# node-circuits.net
KiCad netlist of a schematic drawn in Altium Designer
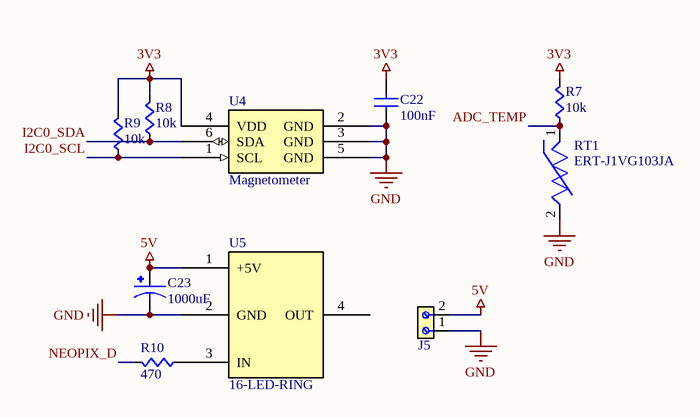
[diagram p0: node-circuits.SchDoc]

(export (version "E")
  (design (tool "Eeschema 10.0.6"))
  (components
    (comp (ref "C22")
      (value "100nF")
      (footprint "CAPC0603")
      (fields (field (name "Comment") "Cap"))
      (libsource (lib "Passives") (part "Cap"))
    )
    (comp (ref "C23")
      (value "1000uF")
      (footprint "CAPPRD350W60D800H1150")
      (description "EEUFM1H101. Cap Aluminum Lytic 100uF 50V 20% (8 X 11.5mm) Radial 3.5mm 870mA 3000h 105?ÂÂŽ Bulk")
      (fields (field (name "MP") "EEUFM1H101") (field (name "MF") "Panasonic"))
      (libsource (lib "Alexandria") (part "EEUFM1H101"))
    )
    (comp (ref "J5")
      (value "[Connector] 691213510002")
      (footprint "[CONNECTOR] 5MM_2PORT_SCREW")
      (description "2 Position Wire to Board Terminal Block Horizontal with Board 0.200 (5.08mm) Through Hole")
      (fields (field (name "MF") "WÃ¼rth Elektronik") (field (name "MP") "691213510002"))
      (libsource (lib "Alexandria") (part "[Connector] 691213510002"))
    )
    (comp (ref "R7")
      (value "10k")
      (footprint "RES0603")
      (description "SMD, RES0603")
      (fields (field (name "Comment") "Res"))
      (libsource (lib "Passives") (part "Res"))
    )
    (comp (ref "R8")
      (value "10k")
      (footprint "RES0603")
      (description "SMD, RES0603")
      (fields (field (name "Comment") "Res"))
      (libsource (lib "Passives") (part "Res"))
    )
    (comp (ref "R9")
      (value "10k")
      (footprint "RES0603")
      (description "SMD, RES0603")
      (fields (field (name "Comment") "Res"))
      (libsource (lib "Passives") (part "Res"))
    )
    (comp (ref "R10")
      (value "470")
      (footprint "RES0603")
      (description "SMD, RES0603")
      (fields (field (name "Comment") "Res"))
      (libsource (lib "Passives") (part "Res"))
    )
    (comp (ref "RT1")
      (value "ERT-J1VG103JA")
      (footprint "THERM_ERT-J1VG103JA")
      (fields (field (name "MF") "Panasonic Electronic"))
      (libsource (lib "Alexandria") (part "ERT-J1VG103JA"))
    )
    (comp (ref "U4")
      (value "Magnetometer")
      (footprint "PG-TSOP6-6-5_INF")
      (fields
        (field (name "MANUFACTURER_PART_NUMBER") "TLV493DA1B6HTSA2")
        (field (name "COPYRIGHT") "Copyright (C) 2025 Ultra Librarian. All rights reserved.")
      )
      (libsource (lib "Alexandria") (part "TLV493DA1B6HTSA2"))
    )
    (comp (ref "U5")
      (value "16-LED-RING")
      (footprint "WS2812-16-RING")
      (description "16-LED Ring, RGB WS2812 neopixels")
      (libsource (lib "Alexandria") (part "WS2812B-16-LED-RING"))
    )
  )
  (nets
    (net (code "1") (name "/ADC_TEMP") (class "Default")
      (node (ref "R7") (pin "2") (pinfunction "B_2") (pintype "passive"))
      (node (ref "RT1") (pin "1") (pinfunction "1_1") (pintype "passive"))
    )
    (net (code "2") (name "/I2C0_SCL") (class "Default")
      (node (ref "R9") (pin "2") (pinfunction "B_2") (pintype "passive"))
      (node (ref "U4") (pin "1") (pinfunction "SCL_1") (pintype "input"))
    )
    (net (code "3") (name "/I2C0_SDA") (class "Default")
      (node (ref "R8") (pin "2") (pinfunction "B_2") (pintype "passive"))
      (node (ref "U4") (pin "6") (pinfunction "SDA_6") (pintype "bidirectional"))
    )
    (net (code "4") (name "/NEOPIX_D") (class "Default")
      (node (ref "R10") (pin "1") (pinfunction "A_1") (pintype "passive"))
    )
    (net (code "5") (name "3V3") (class "Default")
      (node (ref "C22") (pin "1") (pinfunction "A_1") (pintype "passive"))
      (node (ref "R7") (pin "1") (pinfunction "A_1") (pintype "passive"))
      (node (ref "R8") (pin "1") (pinfunction "A_1") (pintype "passive"))
      (node (ref "R9") (pin "1") (pinfunction "A_1") (pintype "passive"))
      (node (ref "U4") (pin "4") (pinfunction "VDD_4") (pintype "power_in"))
    )
    (net (code "6") (name "5V") (class "Default")
      (node (ref "C23") (pin "P") (pinfunction "P_P") (pintype "passive"))
      (node (ref "J5") (pin "2") (pinfunction "2_2") (pintype "passive"))
      (node (ref "U5") (pin "1") (pinfunction "+5V_1") (pintype "passive"))
    )
    (net (code "7") (name "GND") (class "Default")
      (node (ref "C22") (pin "2") (pinfunction "B_2") (pintype "passive"))
      (node (ref "C23") (pin "N") (pinfunction "N_N") (pintype "passive"))
      (node (ref "J5") (pin "1") (pinfunction "1_1") (pintype "passive"))
      (node (ref "RT1") (pin "2") (pinfunction "2_2") (pintype "passive"))
      (node (ref "U4") (pin "2") (pinfunction "GND_2") (pintype "power_in"))
      (node (ref "U4") (pin "3") (pinfunction "GND_3") (pintype "power_in"))
      (node (ref "U4") (pin "5") (pinfunction "GND_5") (pintype "power_in"))
      (node (ref "U5") (pin "2") (pinfunction "GND_2") (pintype "passive"))
    )
    (net (code "8") (name "Net-(R10-B)") (class "Default")
      (node (ref "R10") (pin "2") (pinfunction "B_2") (pintype "passive"))
      (node (ref "U5") (pin "3") (pinfunction "IN_3") (pintype "passive"))
    )
    (net (code "9") (name "unconnected-(U5-OUT-Pad4)") (class "Default")
      (node (ref "U5") (pin "4") (pinfunction "OUT_4") (pintype "passive"))
    )
  )
)
